# 10-MODEM.net
KiCad netlist of a schematic drawn in Altium Designer
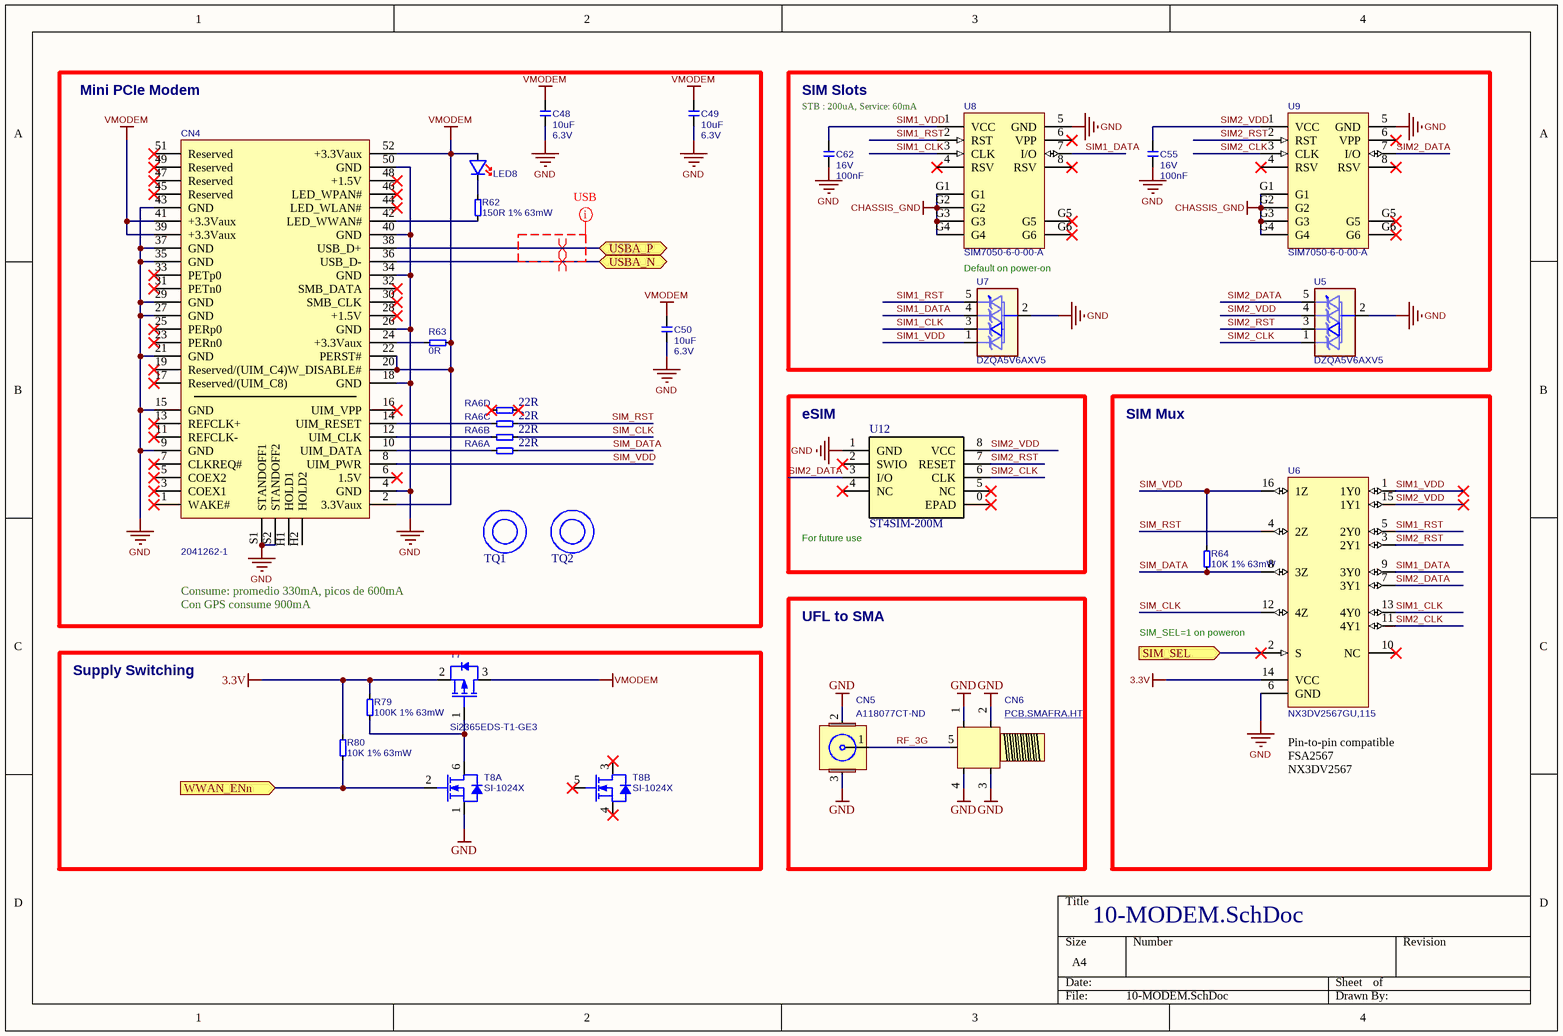
[diagram p0: 10-MODEM.SchDoc]

(export (version "E")
  (design (tool "Eeschema 10.0.6"))
  (components
    (comp (ref "C48")
      (value "10uF")
      (footprint "T_CAPC0603X33N")
      (description "Capacitor Ceramic X5R 10uF 6.3V 20% 0603")
      (fields
        (field (name "TOLERANCE") "20%")
        (field (name "RATING") "6.3V")
        (field (name "Comment") "10uF 6.3V 20% X5R")
      )
      (libsource (lib "AI Gateway - Carrier") (part "C-10uF-6.3V-20%-0603"))
    )
    (comp (ref "C49")
      (value "10uF")
      (footprint "T_CAPC0603X33N")
      (description "Capacitor Ceramic X5R 10uF 6.3V 20% 0603")
      (fields
        (field (name "TOLERANCE") "20%")
        (field (name "RATING") "6.3V")
        (field (name "Comment") "10uF 6.3V 20% X5R")
      )
      (libsource (lib "AI Gateway - Carrier") (part "C-10uF-6.3V-20%-0603"))
    )
    (comp (ref "C50")
      (value "10uF")
      (footprint "T_CAPC0603X33N")
      (description "Capacitor Ceramic X5R 10uF 6.3V 20% 0603")
      (fields
        (field (name "TOLERANCE") "20%")
        (field (name "RATING") "6.3V")
        (field (name "Comment") "10uF 6.3V 20% X5R")
      )
      (libsource (lib "AI Gateway - Carrier") (part "C-10uF-6.3V-20%-0603"))
    )
    (comp (ref "C55")
      (value "100nF")
      (footprint "CAPC1005X60N")
      (description "Capacitor Ceramic X7R 100nF 16V 10% 0603")
      (fields
        (field (name "TOLERANCE") "10%")
        (field (name "RATING") "16V")
        (field (name "Comment") "100nF 16V 10% X7R")
      )
      (libsource (lib "AI Gateway - Carrier") (part "C-100nF-16V-10%-0603"))
    )
    (comp (ref "C62")
      (value "100nF")
      (footprint "CAPC1005X60N")
      (description "Capacitor Ceramic X7R 100nF 16V 10% 0603")
      (fields
        (field (name "TOLERANCE") "10%")
        (field (name "RATING") "16V")
        (field (name "Comment") "100nF 16V 10% X7R")
      )
      (libsource (lib "AI Gateway - Carrier") (part "C-100nF-16V-10%-0603"))
    )
    (comp (ref "CN4")
      (value "2041262-1")
      (footprint "2041262-1")
      (description "52 Position Female Connector PCI Express Mini Card Gold 0.031\" (0.80mm) Black")
      (fields (field (name "MFG") "TE") (field (name "FOOTPRINT CHECKED") "Assign OK, Footprint OK"))
      (libsource (lib "Connectors") (part "CON-TE-2041262-1"))
    )
    (comp (ref "CN5")
      (value "A118077CT-ND")
      (footprint "U.FL-R-SMT-1")
      (description "U.FL (UMCC) Connector Jack, Male Pin 50Ohm Surface Mount Solder")
      (fields
        (field (name "MFG") "TE Connectivity AMP Connectors")
        (field (name "FOOTPRINT CHECKED") "Assign OK, Footprint OK")
      )
      (libsource (lib "Connectors") (part "CON-TE-A118077CT-ND"))
    )
    (comp (ref "CN6")
      (value "PCB.SMAFRA.HT")
      (footprint "0733910320")
      (description "SMA Connector Jack, Female Socket 50Ohm Through Hole, Right Angle Solder")
      (fields
        (field (name "MFG") "Taoglas Limited")
        (field (name "FOOTPRINT CHECKED") "Assign OK, Footprint OK")
      )
      (libsource (lib "Connectors") (part "CON-Taoglas-PCB.SMAFRA.HT"))
    )
    (comp (ref "LED8")
      (value "150060RS75000")
      (footprint "LEDC1608X80N")
      (description "Red 625nm LED Indication - Discrete 2V 0603 (1608 Metric)")
      (fields (field (name "MFG") "Würth Elektronik"))
      (libsource (lib "AI Gateway - Carrier") (part "LED-RED-0603"))
    )
    (comp (ref "R62")
      (value "150R 1% 63mW")
      (footprint "RESC1005X40N")
      (description "Resistor 150ohm 63mW 1% 0402")
      (fields (field (name "POWER") "63mW") (field (name "TOLERANCE") "1%"))
      (libsource (lib "AI Gateway - Carrier") (part "R-150R-1%-0402"))
    )
    (comp (ref "R63")
      (value "0R")
      (footprint "RESC1005X40N")
      (description "Resistor 0ohm 0402")
      (fields (field (name "POWER") "?") (field (name "TOLERANCE") "1%"))
      (libsource (lib "AI Gateway - Carrier") (part "R-0R-0402"))
    )
    (comp (ref "R64")
      (value "10K 1% 63mW")
      (footprint "RESC1005X40N")
      (description "Resistor 10Kohm 63mW 1% 0402")
      (fields (field (name "POWER") "63mW") (field (name "TOLERANCE") "1%"))
      (libsource (lib "AI Gateway - Carrier") (part "R-10K-1%-0402"))
    )
    (comp (ref "R79")
      (value "100K 1% 63mW")
      (footprint "RESC1005X40N")
      (description "Resistor 100Kohm 63mW 1% 0402")
      (fields (field (name "POWER") "63mW") (field (name "TOLERANCE") "1%"))
      (libsource (lib "AI Gateway - Carrier") (part "R-100K-1%-0402"))
    )
    (comp (ref "R80")
      (value "10K 1% 63mW")
      (footprint "RESC1005X40N")
      (description "Resistor 10Kohm 63mW 1% 0402")
      (fields (field (name "POWER") "63mW") (field (name "TOLERANCE") "1%"))
      (libsource (lib "AI Gateway - Carrier") (part "R-10K-1%-0402"))
    )
    (comp (ref "RA6")
      (value "22R")
      (footprint "T_Resistor_Array_X4")
      (description "Resistor Array 22 R 63mW 5% 1206")
      (fields (field (name "TOLERANCE") "5%") (field (name "MFG") "Generic"))
      (libsource (lib "Passive") (part "RA-22R-5%-1206-div"))
    )
    (comp (ref "T7")
      (value "Si2365EDS-T1-GE3")
      (footprint "SOT95P230X110-3N")
      (description "MOSFET, P channel Vishay Si2365EDS-T1-GE3")
      (fields (field (name "MFG") "VISHAY"))
      (libsource (lib "AI Gateway - Carrier") (part "T-Vishay-Si2365EDS"))
    )
    (comp (ref "T8")
      (value "SI-1024X")
      (footprint "SOTFL50P160X60-6N")
      (description "Mosfet Array 2 N-Channel (Dual) 20V 485mA 250mW Surface Mount SC-89-6")
      (fields (field (name "MFG") "Vishay"))
      (libsource (lib "AI Gateway - Carrier") (part "T-Vishay-SI-1024X"))
    )
    (comp (ref "TQ1")
      (value "9774040243R")
      (description "ROUND STANDOFF M2X0.4 STEEL 4MM")
      (fields (field (name "MFG") "Wurth"))
      (libsource (lib "AI Gateway - Carrier") (part "MECH-Wurth-9774040243R"))
    )
    (comp (ref "TQ2")
      (value "9774040243R")
      (description "ROUND STANDOFF M2X0.4 STEEL 4MM")
      (fields (field (name "MFG") "Wurth"))
      (libsource (lib "AI Gateway - Carrier") (part "MECH-Wurth-9774040243R"))
    )
    (comp (ref "U5")
      (value "DZQA5V6AXV5")
      (footprint "SOTFL50P162X62-5N")
      (description "13V Clamp 2.5A (8/20µs) Ipp Tvs Diode Surface Mount 5-TSSOP")
      (fields (field (name "MFG") "DIODES") (field (name "FOOTPRINT CHECKED") "Assign OK, Footprint OK"))
      (libsource (lib "Passive") (part "D-DZQA5V6AXV5"))
    )
    (comp (ref "U6")
      (value "NX3DV2567GU,115")
      (footprint "XFQFN-16")
      (description "Networking Switch IC 1 Channel 16-XQFN (1.8x2.6)")
      (fields (field (name "MFG") "NXP") (field (name "SYMBOL CHECKED") "D"))
      (libsource (lib "AIGateway") (part "IC-NXP-NX3DV2567"))
    )
    (comp (ref "U7")
      (value "DZQA5V6AXV5")
      (footprint "SOTFL50P162X62-5N")
      (description "13V Clamp 2.5A (8/20µs) Ipp Tvs Diode Surface Mount 5-TSSOP")
      (fields (field (name "MFG") "DIODES") (field (name "FOOTPRINT CHECKED") "Assign OK, Footprint OK"))
      (libsource (lib "Passive") (part "D-DZQA5V6AXV5"))
    )
    (comp (ref "U8")
      (value "SIM7050-6-0-00-A")
      (footprint "SIM7050-8-0-00-X_revC")
      (description "MICRO SIM PUSH-PUSH, 6P, SMT, 1.")
      (fields (field (name "MFG") "GCT") (field (name "FOOTPRINT CHECKED") "Assign OK, Footprint OK"))
      (libsource (lib "Connectors") (part "CON-Molex-115I-AEAA"))
    )
    (comp (ref "U9")
      (value "SIM7050-6-0-00-A")
      (footprint "SIM7050-8-0-00-X_revC")
      (description "MICRO SIM PUSH-PUSH, 6P, SMT, 1.")
      (fields (field (name "MFG") "GCT") (field (name "FOOTPRINT CHECKED") "Assign OK, Footprint OK"))
      (libsource (lib "Connectors") (part "CON-Molex-115I-AEAA"))
    )
    (comp (ref "U12")
      (value "ST4SIM-200M")
      (footprint "ST4SIM-200M")
      (description "ESIM SYSTEM ON CHIP FOR M2M INDU")
      (fields (field (name "MFG") "STMicroelectronics"))
      (libsource (lib "AI Gateway - Carrier") (part "IC-ST-ST4SIM-200M"))
    )
  )
  (nets
    (net (code "1") (name "/RF_3G") (class "Default")
      (node (ref "CN5") (pin "1") (pinfunction "SIG_1") (pintype "passive"))
      (node (ref "CN6") (pin "5") (pinfunction "SIG_5") (pintype "passive"))
    )
    (net (code "2") (name "/SIM1_CLK") (class "Default")
      (node (ref "U6") (pin "13") (pinfunction "4Y0_13") (pintype "bidirectional"))
      (node (ref "U7") (pin "3") (pinfunction "3_3") (pintype "passive"))
      (node (ref "U8") (pin "3") (pinfunction "CLK_3") (pintype "input"))
    )
    (net (code "3") (name "/SIM1_DATA") (class "Default")
      (node (ref "U6") (pin "9") (pinfunction "3Y0_9") (pintype "bidirectional"))
      (node (ref "U7") (pin "4") (pinfunction "4_4") (pintype "passive"))
      (node (ref "U8") (pin "7") (pinfunction "I/O_7") (pintype "bidirectional"))
    )
    (net (code "4") (name "/SIM1_RST") (class "Default")
      (node (ref "U6") (pin "5") (pinfunction "2Y0_5") (pintype "bidirectional"))
      (node (ref "U7") (pin "5") (pinfunction "5_5") (pintype "passive"))
      (node (ref "U8") (pin "2") (pinfunction "RST_2") (pintype "input"))
    )
    (net (code "5") (name "/SIM1_VDD") (class "Default")
      (node (ref "C62") (pin "1") (pinfunction "1_1") (pintype "passive"))
      (node (ref "U6") (pin "1") (pinfunction "1Y0_1") (pintype "bidirectional"))
      (node (ref "U7") (pin "1") (pinfunction "1_1") (pintype "passive"))
      (node (ref "U8") (pin "1") (pinfunction "VCC_1") (pintype "power_in"))
    )
    (net (code "6") (name "/SIM2_CLK") (class "Default")
      (node (ref "U12") (pin "6") (pinfunction "CLK_6") (pintype "passive"))
      (node (ref "U5") (pin "1") (pinfunction "1_1") (pintype "passive"))
      (node (ref "U6") (pin "11") (pinfunction "4Y1_11") (pintype "bidirectional"))
      (node (ref "U9") (pin "3") (pinfunction "CLK_3") (pintype "input"))
    )
    (net (code "7") (name "/SIM2_DATA") (class "Default")
      (node (ref "U12") (pin "3") (pinfunction "I/O_3") (pintype "passive"))
      (node (ref "U5") (pin "5") (pinfunction "5_5") (pintype "passive"))
      (node (ref "U6") (pin "7") (pinfunction "3Y1_7") (pintype "bidirectional"))
      (node (ref "U9") (pin "7") (pinfunction "I/O_7") (pintype "bidirectional"))
    )
    (net (code "8") (name "/SIM2_RST") (class "Default")
      (node (ref "U12") (pin "7") (pinfunction "RESET_7") (pintype "passive"))
      (node (ref "U5") (pin "3") (pinfunction "3_3") (pintype "passive"))
      (node (ref "U6") (pin "3") (pinfunction "2Y1_3") (pintype "bidirectional"))
      (node (ref "U9") (pin "2") (pinfunction "RST_2") (pintype "input"))
    )
    (net (code "9") (name "/SIM2_VDD") (class "Default")
      (node (ref "C55") (pin "1") (pinfunction "1_1") (pintype "passive"))
      (node (ref "U12") (pin "8") (pinfunction "VCC_8") (pintype "power_in"))
      (node (ref "U5") (pin "4") (pinfunction "4_4") (pintype "passive"))
      (node (ref "U6") (pin "15") (pinfunction "1Y1_15") (pintype "bidirectional"))
      (node (ref "U9") (pin "1") (pinfunction "VCC_1") (pintype "power_in"))
    )
    (net (code "10") (name "/SIM_CLK") (class "Default")
      (node (ref "RA6") (pin "6") (pinfunction "6_6") (pintype "passive"))
      (node (ref "U6") (pin "12") (pinfunction "4Z_12") (pintype "bidirectional"))
    )
    (net (code "11") (name "/SIM_DATA") (class "Default")
      (node (ref "R64") (pin "1") (pinfunction "1_1") (pintype "passive"))
      (node (ref "RA6") (pin "5") (pinfunction "5_5") (pintype "passive"))
      (node (ref "U6") (pin "8") (pinfunction "3Z_8") (pintype "bidirectional"))
    )
    (net (code "12") (name "/SIM_RST") (class "Default")
      (node (ref "RA6") (pin "7") (pinfunction "7_7") (pintype "passive"))
      (node (ref "U6") (pin "4") (pinfunction "2Z_4") (pintype "bidirectional"))
    )
    (net (code "13") (name "/SIM_SEL") (class "Default")
      (node (ref "U6") (pin "2") (pinfunction "S_2") (pintype "input+no_connect"))
    )
    (net (code "14") (name "/SIM_VDD") (class "Default")
      (node (ref "CN4") (pin "8") (pinfunction "UIM_PWR_8") (pintype "passive"))
      (node (ref "R64") (pin "2") (pinfunction "2_2") (pintype "passive"))
      (node (ref "U6") (pin "16") (pinfunction "1Z_16") (pintype "bidirectional"))
    )
    (net (code "15") (name "/USBA_N") (class "Default")
      (node (ref "CN4") (pin "36") (pinfunction "USB_D-_36") (pintype "passive"))
    )
    (net (code "16") (name "/USBA_P") (class "Default")
      (node (ref "CN4") (pin "38") (pinfunction "USB_D+_38") (pintype "passive"))
    )
    (net (code "17") (name "/WWAN_ENn") (class "Default")
      (node (ref "R80") (pin "1") (pinfunction "1_1") (pintype "passive"))
      (node (ref "T8") (pin "2") (pinfunction "G_2") (pintype "passive"))
    )
    (net (code "18") (name "3.3V") (class "Default")
      (node (ref "R79") (pin "2") (pinfunction "2_2") (pintype "passive"))
      (node (ref "R80") (pin "2") (pinfunction "2_2") (pintype "passive"))
      (node (ref "T7") (pin "2") (pinfunction "D_2") (pintype "passive"))
      (node (ref "U6") (pin "14") (pinfunction "VCC_14") (pintype "power_in"))
    )
    (net (code "19") (name "CHASSIS_GND") (class "Default")
      (node (ref "U8") (pin "G1") (pinfunction "G1_G1") (pintype "passive"))
      (node (ref "U8") (pin "G2") (pinfunction "G2_G2") (pintype "passive"))
      (node (ref "U8") (pin "G3") (pinfunction "G3_G3") (pintype "passive"))
      (node (ref "U8") (pin "G4") (pinfunction "G4_G4") (pintype "passive"))
      (node (ref "U9") (pin "G1") (pinfunction "G1_G1") (pintype "passive"))
      (node (ref "U9") (pin "G2") (pinfunction "G2_G2") (pintype "passive"))
      (node (ref "U9") (pin "G3") (pinfunction "G3_G3") (pintype "passive"))
      (node (ref "U9") (pin "G4") (pinfunction "G4_G4") (pintype "passive"))
    )
    (net (code "20") (name "GND") (class "Default")
      (node (ref "C48") (pin "2") (pinfunction "2_2") (pintype "passive"))
      (node (ref "C49") (pin "2") (pinfunction "2_2") (pintype "passive"))
      (node (ref "C50") (pin "2") (pinfunction "2_2") (pintype "passive"))
      (node (ref "C55") (pin "2") (pinfunction "2_2") (pintype "passive"))
      (node (ref "C62") (pin "2") (pinfunction "2_2") (pintype "passive"))
      (node (ref "CN4") (pin "15") (pinfunction "GND_15") (pintype "passive"))
      (node (ref "CN4") (pin "18") (pinfunction "GND_18") (pintype "passive"))
      (node (ref "CN4") (pin "21") (pinfunction "GND_21") (pintype "passive"))
      (node (ref "CN4") (pin "26") (pinfunction "GND_26") (pintype "passive"))
      (node (ref "CN4") (pin "27") (pinfunction "GND_27") (pintype "passive"))
      (node (ref "CN4") (pin "29") (pinfunction "GND_29") (pintype "passive"))
      (node (ref "CN4") (pin "34") (pinfunction "GND_34") (pintype "passive"))
      (node (ref "CN4") (pin "35") (pinfunction "GND_35") (pintype "passive"))
      (node (ref "CN4") (pin "37") (pinfunction "GND_37") (pintype "passive"))
      (node (ref "CN4") (pin "4") (pinfunction "GND_4") (pintype "passive"))
      (node (ref "CN4") (pin "40") (pinfunction "GND_40") (pintype "passive"))
      (node (ref "CN4") (pin "43") (pinfunction "GND_43") (pintype "passive"))
      (node (ref "CN4") (pin "50") (pinfunction "GND_50") (pintype "passive"))
      (node (ref "CN4") (pin "9") (pinfunction "GND_9") (pintype "passive"))
      (node (ref "CN4") (pin "S1") (pinfunction "STANDOFF1_S1") (pintype "passive"))
      (node (ref "CN4") (pin "S2") (pinfunction "STANDOFF2_S2") (pintype "passive"))
      (node (ref "CN5") (pin "2") (pinfunction "GND_2") (pintype "passive"))
      (node (ref "CN5") (pin "3") (pinfunction "GND_3") (pintype "passive"))
      (node (ref "CN6") (pin "1") (pinfunction "GND_1") (pintype "passive"))
      (node (ref "CN6") (pin "2") (pinfunction "GND_2") (pintype "passive"))
      (node (ref "CN6") (pin "3") (pinfunction "GND_3") (pintype "passive"))
      (node (ref "CN6") (pin "4") (pinfunction "GND_4") (pintype "passive"))
      (node (ref "T8") (pin "1") (pinfunction "S_1") (pintype "passive"))
      (node (ref "U12") (pin "1") (pinfunction "GND_1") (pintype "passive"))
      (node (ref "U5") (pin "2") (pinfunction "2_2") (pintype "passive"))
      (node (ref "U6") (pin "6") (pinfunction "GND_6") (pintype "power_in"))
      (node (ref "U7") (pin "2") (pinfunction "2_2") (pintype "passive"))
      (node (ref "U8") (pin "5") (pinfunction "GND_5") (pintype "power_in"))
      (node (ref "U9") (pin "5") (pinfunction "GND_5") (pintype "power_in"))
    )
    (net (code "21") (name "Net-(CN4-+3.3Vaux-Pad24)") (class "Default")
      (node (ref "CN4") (pin "24") (pinfunction "+3.3Vaux_24") (pintype "passive"))
      (node (ref "R63") (pin "2") (pinfunction "2_2") (pintype "passive"))
    )
    (net (code "22") (name "Net-(CN4-LED_WWAN#)") (class "Default")
      (node (ref "CN4") (pin "42") (pinfunction "LED_WWAN#_42") (pintype "passive"))
      (node (ref "R62") (pin "2") (pinfunction "2_2") (pintype "passive"))
    )
    (net (code "23") (name "Net-(CN4-UIM_CLK)") (class "Default")
      (node (ref "CN4") (pin "12") (pinfunction "UIM_CLK_12") (pintype "passive"))
      (node (ref "RA6") (pin "2") (pinfunction "2_2") (pintype "passive"))
    )
    (net (code "24") (name "Net-(CN4-UIM_DATA)") (class "Default")
      (node (ref "CN4") (pin "10") (pinfunction "UIM_DATA_10") (pintype "passive"))
      (node (ref "RA6") (pin "1") (pinfunction "1_1") (pintype "passive"))
    )
    (net (code "25") (name "Net-(CN4-UIM_RESET)") (class "Default")
      (node (ref "CN4") (pin "14") (pinfunction "UIM_RESET_14") (pintype "passive"))
      (node (ref "RA6") (pin "3") (pinfunction "3_3") (pintype "passive"))
    )
    (net (code "26") (name "Net-(LED8-Pad1)") (class "Default")
      (node (ref "LED8") (pin "1") (pinfunction "1_1") (pintype "passive"))
      (node (ref "R62") (pin "1") (pinfunction "1_1") (pintype "passive"))
    )
    (net (code "27") (name "Net-(T7-G)") (class "Default")
      (node (ref "R79") (pin "1") (pinfunction "1_1") (pintype "passive"))
      (node (ref "T7") (pin "1") (pinfunction "G_1") (pintype "passive"))
      (node (ref "T8") (pin "6") (pinfunction "D_6") (pintype "passive"))
    )
    (net (code "28") (name "VMODEM") (class "Default")
      (node (ref "C48") (pin "1") (pinfunction "1_1") (pintype "passive"))
      (node (ref "C49") (pin "1") (pinfunction "1_1") (pintype "passive"))
      (node (ref "C50") (pin "1") (pinfunction "1_1") (pintype "passive"))
      (node (ref "CN4") (pin "2") (pinfunction "3.3Vaux_2") (pintype "passive"))
      (node (ref "CN4") (pin "20") (pinfunction "W_DISABLE#_20") (pintype "passive"))
      (node (ref "CN4") (pin "22") (pinfunction "PERST#_22") (pintype "passive"))
      (node (ref "CN4") (pin "39") (pinfunction "+3.3Vaux_39") (pintype "passive"))
      (node (ref "CN4") (pin "41") (pinfunction "+3.3Vaux_41") (pintype "passive"))
      (node (ref "CN4") (pin "52") (pinfunction "+3.3Vaux_52") (pintype "passive"))
      (node (ref "LED8") (pin "2") (pinfunction "2_2") (pintype "passive"))
      (node (ref "R63") (pin "1") (pinfunction "1_1") (pintype "passive"))
      (node (ref "T7") (pin "3") (pinfunction "S_3") (pintype "passive"))
    )
    (net (code "29") (name "unconnected-(CN4-+1.5V-Pad28)") (class "Default")
      (node (ref "CN4") (pin "28") (pinfunction "+1.5V_28") (pintype "passive+no_connect"))
    )
    (net (code "30") (name "unconnected-(CN4-+1.5V-Pad48)") (class "Default")
      (node (ref "CN4") (pin "48") (pinfunction "+1.5V_48") (pintype "passive+no_connect"))
    )
    (net (code "31") (name "unconnected-(CN4-1.5V-Pad6)") (class "Default")
      (node (ref "CN4") (pin "6") (pinfunction "1.5V_6") (pintype "passive+no_connect"))
    )
    (net (code "32") (name "unconnected-(CN4-CLKREQ#-Pad7)") (class "Default")
      (node (ref "CN4") (pin "7") (pinfunction "CLKREQ#_7") (pintype "passive+no_connect"))
    )
    (net (code "33") (name "unconnected-(CN4-COEX1-Pad3)") (class "Default")
      (node (ref "CN4") (pin "3") (pinfunction "COEX1_3") (pintype "passive+no_connect"))
    )
    (net (code "34") (name "unconnected-(CN4-COEX2-Pad5)") (class "Default")
      (node (ref "CN4") (pin "5") (pinfunction "COEX2_5") (pintype "passive+no_connect"))
    )
    (net (code "35") (name "unconnected-(CN4-HOLD1-PadH1)") (class "Default")
      (node (ref "CN4") (pin "H1") (pinfunction "HOLD1_H1") (pintype "passive"))
    )
    (net (code "36") (name "unconnected-(CN4-HOLD2-PadH2)") (class "Default")
      (node (ref "CN4") (pin "H2") (pinfunction "HOLD2_H2") (pintype "passive"))
    )
    (net (code "37") (name "unconnected-(CN4-LED_WLAN#-Pad44)") (class "Default")
      (node (ref "CN4") (pin "44") (pinfunction "LED_WLAN#_44") (pintype "passive+no_connect"))
    )
    (net (code "38") (name "unconnected-(CN4-LED_WPAN#-Pad46)") (class "Default")
      (node (ref "CN4") (pin "46") (pinfunction "LED_WPAN#_46") (pintype "passive+no_connect"))
    )
    (net (code "39") (name "unconnected-(CN4-PERn0-Pad23)") (class "Default")
      (node (ref "CN4") (pin "23") (pinfunction "PERn0_23") (pintype "passive+no_connect"))
    )
    (net (code "40") (name "unconnected-(CN4-PERp0-Pad25)") (class "Default")
      (node (ref "CN4") (pin "25") (pinfunction "PERp0_25") (pintype "passive+no_connect"))
    )
    (net (code "41") (name "unconnected-(CN4-PETn0-Pad31)") (class "Default")
      (node (ref "CN4") (pin "31") (pinfunction "PETn0_31") (pintype "passive+no_connect"))
    )
    (net (code "42") (name "unconnected-(CN4-PETp0-Pad33)") (class "Default")
      (node (ref "CN4") (pin "33") (pinfunction "PETp0_33") (pintype "passive+no_connect"))
    )
    (net (code "43") (name "unconnected-(CN4-REFCLK+-Pad13)") (class "Default")
      (node (ref "CN4") (pin "13") (pinfunction "REFCLK+_13") (pintype "passive+no_connect"))
    )
    (net (code "44") (name "unconnected-(CN4-REFCLK--Pad11)") (class "Default")
      (node (ref "CN4") (pin "11") (pinfunction "REFCLK-_11") (pintype "passive+no_connect"))
    )
    (net (code "45") (name "unconnected-(CN4-Reserved-Pad45)") (class "Default")
      (node (ref "CN4") (pin "45") (pinfunction "Reserved_45") (pintype "passive+no_connect"))
    )
    (net (code "46") (name "unconnected-(CN4-Reserved-Pad47)") (class "Default")
      (node (ref "CN4") (pin "47") (pinfunction "Reserved_47") (pintype "passive+no_connect"))
    )
    (net (code "47") (name "unconnected-(CN4-Reserved-Pad49)") (class "Default")
      (node (ref "CN4") (pin "49") (pinfunction "Reserved_49") (pintype "passive+no_connect"))
    )
    (net (code "48") (name "unconnected-(CN4-Reserved-Pad51)") (class "Default")
      (node (ref "CN4") (pin "51") (pinfunction "Reserved_51") (pintype "passive+no_connect"))
    )
    (net (code "49") (name "unconnected-(CN4-Reserved{slash}(UIM_C4)-Pad19)") (class "Default")
      (node (ref "CN4") (pin "19") (pinfunction "Reserved/(UIM_C4)_19") (pintype "passive+no_connect"))
    )
    (net (code "50") (name "unconnected-(CN4-Reserved{slash}(UIM_C8)-Pad17)") (class "Default")
      (node (ref "CN4") (pin "17") (pinfunction "Reserved/(UIM_C8)_17") (pintype "passive+no_connect"))
    )
    (net (code "51") (name "unconnected-(CN4-SMB_CLK-Pad30)") (class "Default")
      (node (ref "CN4") (pin "30") (pinfunction "SMB_CLK_30") (pintype "passive+no_connect"))
    )
    (net (code "52") (name "unconnected-(CN4-SMB_DATA-Pad32)") (class "Default")
      (node (ref "CN4") (pin "32") (pinfunction "SMB_DATA_32") (pintype "passive+no_connect"))
    )
    (net (code "53") (name "unconnected-(CN4-UIM_VPP-Pad16)") (class "Default")
      (node (ref "CN4") (pin "16") (pinfunction "UIM_VPP_16") (pintype "passive+no_connect"))
    )
    (net (code "54") (name "unconnected-(CN4-WAKE#-Pad1)") (class "Default")
      (node (ref "CN4") (pin "1") (pinfunction "WAKE#_1") (pintype "passive+no_connect"))
    )
    (net (code "55") (name "unconnected-(RA6-Pad4)") (class "Default")
      (node (ref "RA6") (pin "4") (pinfunction "4_4") (pintype "passive+no_connect"))
    )
    (net (code "56") (name "unconnected-(RA6-Pad8)") (class "Default")
      (node (ref "RA6") (pin "8") (pinfunction "8_8") (pintype "passive+no_connect"))
    )
    (net (code "57") (name "unconnected-(T8B-D-Pad3)") (class "Default")
      (node (ref "T8") (pin "3") (pinfunction "D_3") (pintype "passive+no_connect"))
    )
    (net (code "58") (name "unconnected-(T8B-G-Pad5)") (class "Default")
      (node (ref "T8") (pin "5") (pinfunction "G_5") (pintype "passive+no_connect"))
    )
    (net (code "59") (name "unconnected-(T8B-S-Pad4)") (class "Default")
      (node (ref "T8") (pin "4") (pinfunction "S_4") (pintype "passive+no_connect"))
    )
    (net (code "60") (name "unconnected-(U6-NC-Pad10)") (class "Default")
      (node (ref "U6") (pin "10") (pinfunction "NC_10") (pintype "passive+no_connect"))
    )
    (net (code "61") (name "unconnected-(U8-PadG5)") (class "Default")
      (node (ref "U8") (pin "G5") (pinfunction "G5_G5") (pintype "passive+no_connect"))
    )
    (net (code "62") (name "unconnected-(U8-PadG6)") (class "Default")
      (node (ref "U8") (pin "G6") (pinfunction "G6_G6") (pintype "passive+no_connect"))
    )
    (net (code "63") (name "unconnected-(U8-RSV-Pad4)") (class "Default")
      (node (ref "U8") (pin "4") (pinfunction "RSV_4") (pintype "passive+no_connect"))
    )
    (net (code "64") (name "unconnected-(U8-RSV-Pad8)") (class "Default")
      (node (ref "U8") (pin "8") (pinfunction "RSV_8") (pintype "passive+no_connect"))
    )
    (net (code "65") (name "unconnected-(U8-VPP-Pad6)") (class "Default")
      (node (ref "U8") (pin "6") (pinfunction "VPP_6") (pintype "power_in+no_connect"))
    )
    (net (code "66") (name "unconnected-(U9-PadG5)") (class "Default")
      (node (ref "U9") (pin "G5") (pinfunction "G5_G5") (pintype "passive+no_connect"))
    )
    (net (code "67") (name "unconnected-(U9-PadG6)") (class "Default")
      (node (ref "U9") (pin "G6") (pinfunction "G6_G6") (pintype "passive+no_connect"))
    )
    (net (code "68") (name "unconnected-(U9-RSV-Pad4)") (class "Default")
      (node (ref "U9") (pin "4") (pinfunction "RSV_4") (pintype "passive+no_connect"))
    )
    (net (code "69") (name "unconnected-(U9-RSV-Pad8)") (class "Default")
      (node (ref "U9") (pin "8") (pinfunction "RSV_8") (pintype "passive+no_connect"))
    )
    (net (code "70") (name "unconnected-(U9-VPP-Pad6)") (class "Default")
      (node (ref "U9") (pin "6") (pinfunction "VPP_6") (pintype "power_in+no_connect"))
    )
    (net (code "71") (name "unconnected-(U12-EPAD-Pad0)") (class "Default")
      (node (ref "U12") (pin "0") (pinfunction "EPAD_0") (pintype "passive+no_connect"))
    )
    (net (code "72") (name "unconnected-(U12-NC-Pad4)") (class "Default")
      (node (ref "U12") (pin "4") (pinfunction "NC_4") (pintype "passive+no_connect"))
    )
    (net (code "73") (name "unconnected-(U12-NC-Pad5)") (class "Default")
      (node (ref "U12") (pin "5") (pinfunction "NC_5") (pintype "passive+no_connect"))
    )
    (net (code "74") (name "unconnected-(U12-SWIO-Pad2)") (class "Default")
      (node (ref "U12") (pin "2") (pinfunction "SWIO_2") (pintype "passive+no_connect"))
    )
  )
)
